# CPU_microcontroler.net
KiCad netlist of a schematic drawn in Altium Designer
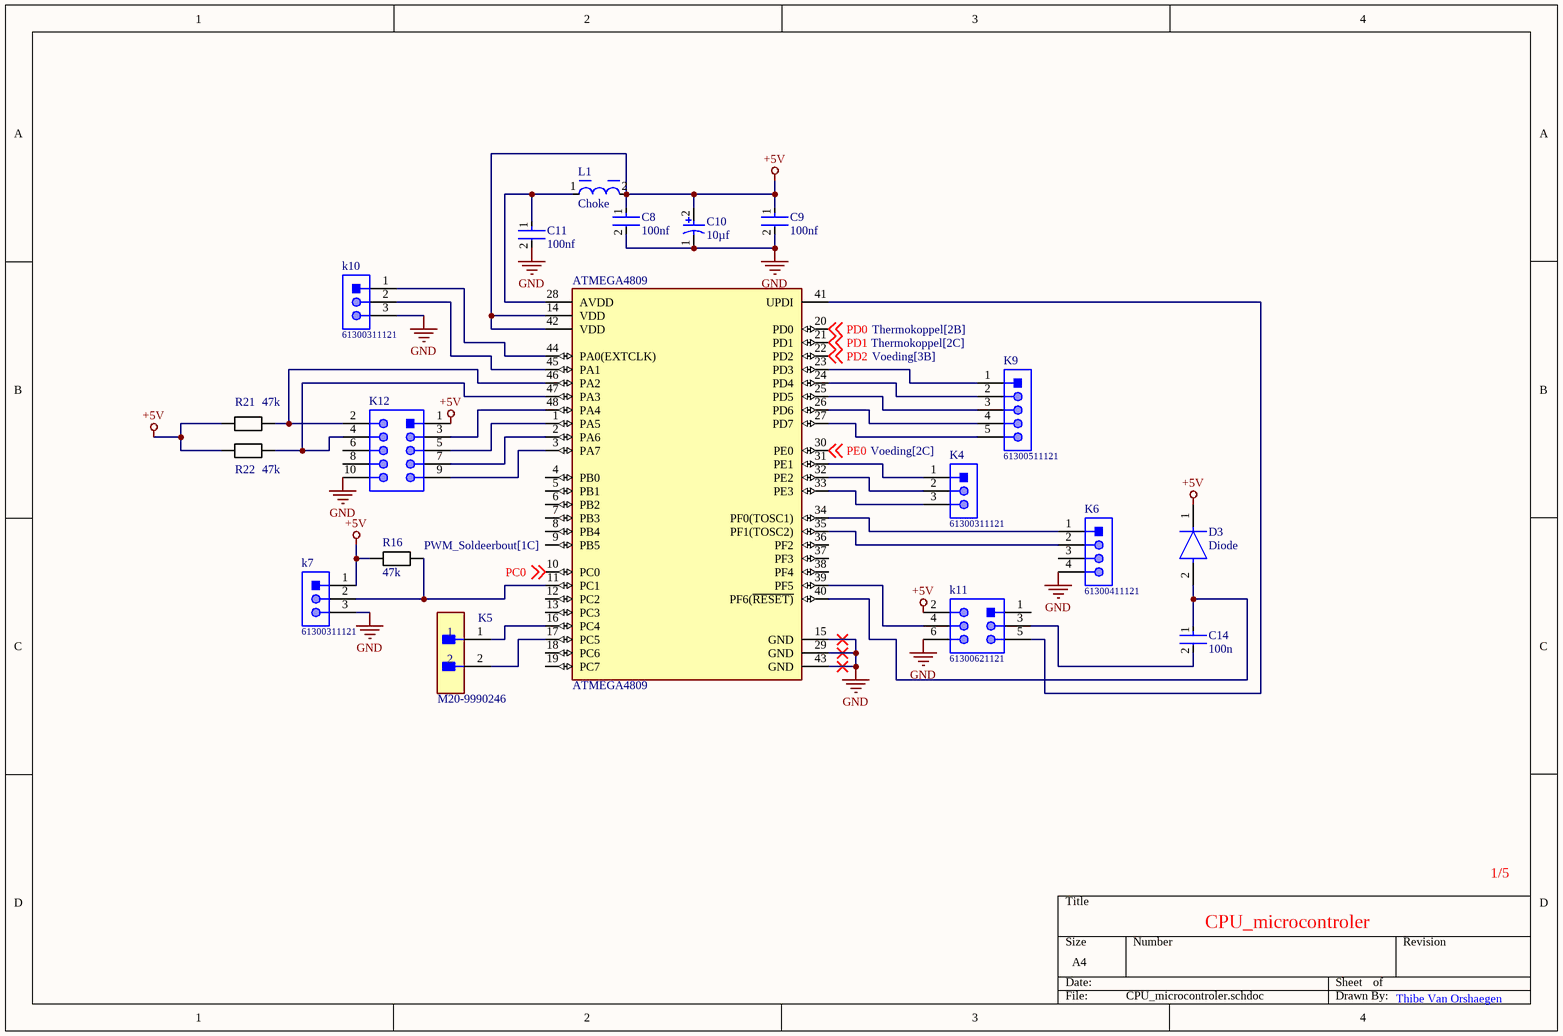
[diagram p0: CPU_microcontroler.schdoc]

(export (version "E")
  (design (tool "Eeschema 10.0.6"))
  (components
    (comp (ref "ATMEGA4809")
      (value "ATMEGA4809")
      (footprint "TQFP_48_M")
      (libsource (lib "Soldeerstation") (part "ATMEGA4809"))
    )
    (comp (ref "C8")
      (value "100nf")
      (footprint "CC_0805_m")
      (fields
        (field (name "MANUFACTURER") "KEMET")
        (field (name "OCTOPART") "https://octopart.com/c0805c224k5ractu-kemet-144670")
        (field (name "MANUFACTURER PART NUMBER") "C0805C224K5RACTU")
      )
      (libsource (lib "Soldeerstation") (part "Capacitor_Ceramic"))
    )
    (comp (ref "C9")
      (value "100nf")
      (footprint "CC_0805_m")
      (fields
        (field (name "MANUFACTURER") "KEMET")
        (field (name "OCTOPART") "https://octopart.com/c0805c224k5ractu-kemet-144670")
        (field (name "MANUFACTURER PART NUMBER") "C0805C224K5RACTU")
      )
      (libsource (lib "Soldeerstation") (part "Capacitor_Ceramic"))
    )
    (comp (ref "C10")
      (value "10µf")
      (footprint "CE_D8_L10")
      (fields (field (name "MANUFACTURER") "Panasonic"))
      (libsource (lib "Soldeerstation") (part "Capacitor_Electrolytic"))
    )
    (comp (ref "C11")
      (value "100nf")
      (footprint "CC_0805_m")
      (fields
        (field (name "MANUFACTURER") "KEMET")
        (field (name "OCTOPART") "https://octopart.com/c0805c224k5ractu-kemet-144670")
        (field (name "MANUFACTURER PART NUMBER") "C0805C224K5RACTU")
      )
      (libsource (lib "Soldeerstation") (part "Capacitor_Ceramic"))
    )
    (comp (ref "C14")
      (value "100n")
      (footprint "CC_0805_m")
      (fields
        (field (name "MANUFACTURER") "KEMET")
        (field (name "OCTOPART") "https://octopart.com/c0805c224k5ractu-kemet-144670")
        (field (name "MANUFACTURER PART NUMBER") "C0805C224K5RACTU")
      )
      (libsource (lib "Soldeerstation") (part "Capacitor_Ceramic"))
    )
    (comp (ref "D3")
      (value "Diode")
      (footprint "SOD-123FL")
      (fields
        (field (name "MANUFACTURER PART NUMBER") "1N4007")
        (field (name "MANUFACTURER") "Diotec")
        (field (name "OCTOPART") "https://octopart.com/1n4007-diotec-4040411")
      )
      (libsource (lib "Soldeerstation") (part "Diode"))
    )
    (comp (ref "K4")
      (value "61300311121")
      (footprint "pin header 1x3")
      (description "THT Vertical Pin Header WR-PHD, Pitch 2.54 mm, Single Row, 3 pins")
      (fields (field (name "MANUFACTURER") "Wurth Elektronik") (field (name "PUBLISHER") "WurthElektronik"))
      (libsource (lib "") (part "pin header 1x3pin_1"))
    )
    (comp (ref "K5")
      (value "M20-9990246")
      (footprint "pin header 1x2")
      (description "CONN HEADER VERT 2POS 2.54MM")
      (fields
        (field (name "OCTOPART") "https://octopart.com/m20-9990246-harwin-2590635")
        (field (name "MANUFACTURER") "Harwin")
      )
      (libsource (lib "Soldeerstation") (part "pin header 1x2"))
    )
    (comp (ref "K6")
      (value "61300411121")
      (footprint "pin header 1x4")
      (description "THT Vertical Pin Header WR-PHD, Pitch 2.54 mm, Single Row, 4 pins")
      (fields (field (name "MANUFACTURER") "Wurth Elektronik") (field (name "PUBLISHER") "WurthElektronik"))
      (libsource (lib "Soldeerstation") (part "pin header 1x4"))
    )
    (comp (ref "k7")
      (value "61300311121")
      (footprint "pin header 1x3")
      (description "THT Vertical Pin Header WR-PHD, Pitch 2.54 mm, Single Row, 3 pins")
      (fields (field (name "MANUFACTURER") "Wurth Elektronik") (field (name "PUBLISHER") "WurthElektronik"))
      (libsource (lib "Soldeerstation") (part "pin header 1x3pin"))
    )
    (comp (ref "K9")
      (value "61300511121")
      (footprint "pin header 1x5")
      (description "THT Vertical Pin Header WR-PHD, Pitch 2.54 mm, Single Row, 5 pins")
      (fields (field (name "MANUFACTURER") "Wurth Elektronik") (field (name "PUBLISHER") "WurthElektronik"))
      (libsource (lib "Soldeerstation") (part "pin header 1x5"))
    )
    (comp (ref "k10")
      (value "61300311121")
      (footprint "pin header 1x3")
      (description "THT Vertical Pin Header WR-PHD, Pitch 2.54 mm, Single Row, 3 pins")
      (fields (field (name "MANUFACTURER") "Wurth Elektronik") (field (name "PUBLISHER") "WurthElektronik"))
      (libsource (lib "Soldeerstation") (part "pin header 1x3pin"))
    )
    (comp (ref "k11")
      (value "61300621121")
      (footprint "pin header 2x6")
      (description "THT Vertical Pin Header WR-PHD, Pitch 2.54 mm, Dual Row, 6 pins")
      (fields (field (name "MANUFACTURER") "Wurth Elektronik") (field (name "PUBLISHER") "WurthElektronik"))
      (libsource (lib "Soldeerstation") (part "pin header 2x6"))
    )
    (comp (ref "K12")
      (value "~")
      (footprint "box header 10-pin")
      (description "Male Box Header WR-BHD, THT, Vertical, pitch 2.54 mm, 10 pins")
      (fields
        (field (name "PART NUMBER") "61201021621")
        (field (name "MANUFACTURER") "Wurth Elektronik")
        (field (name "PUBLISHER") "WurthElektronik")
      )
      (libsource (lib "Soldeerstation") (part "Box Header"))
    )
    (comp (ref "L1")
      (value "Choke")
      (footprint "CC_0805_m")
      (fields (field (name "TOLERANCE") "20%"))
      (libsource (lib "Soldeerstation") (part "Choke"))
    )
    (comp (ref "R16")
      (value "47k")
      (footprint "RESC2013X50X30ML20T20")
      (fields (field (name "MANUFACTURER") "Vishay Dale") (field (name "PART NUMBER") "CRCW08050000Z0EA"))
      (libsource (lib "Soldeerstation") (part "Weerstand"))
    )
    (comp (ref "R21")
      (value "47k")
      (footprint "RESC2013X50X30ML20T20")
      (fields (field (name "MANUFACTURER") "Vishay Dale") (field (name "PART NUMBER") "CRCW08050000Z0EA"))
      (libsource (lib "Soldeerstation") (part "Weerstand"))
    )
    (comp (ref "R22")
      (value "47k")
      (footprint "RESC2013X50X30ML20T20")
      (fields (field (name "MANUFACTURER") "Vishay Dale") (field (name "PART NUMBER") "CRCW08050000Z0EA"))
      (libsource (lib "Soldeerstation") (part "Weerstand"))
    )
  )
  (nets
    (net (code "1") (name "+5V") (class "Default")
      (node (ref "ATMEGA4809") (pin "14") (pinfunction "VDD_14") (pintype "power_in"))
      (node (ref "ATMEGA4809") (pin "42") (pinfunction "VDD_42") (pintype "power_in"))
      (node (ref "C10") (pin "2") (pinfunction "2_2") (pintype "passive"))
      (node (ref "C8") (pin "1") (pinfunction "1_1") (pintype "passive"))
      (node (ref "C9") (pin "1") (pinfunction "1_1") (pintype "passive"))
      (node (ref "D3") (pin "1") (pinfunction "C_1") (pintype "passive"))
      (node (ref "K12") (pin "1") (pinfunction "1_1") (pintype "passive"))
      (node (ref "L1") (pin "2") (pinfunction "2_2") (pintype "passive"))
      (node (ref "R16") (pin "1") (pinfunction "1_1") (pintype "passive"))
      (node (ref "R21") (pin "1") (pinfunction "1_1") (pintype "passive"))
      (node (ref "R22") (pin "1") (pinfunction "1_1") (pintype "passive"))
      (node (ref "k11") (pin "2") (pinfunction "2_2") (pintype "passive"))
      (node (ref "k7") (pin "1") (pinfunction "1_1") (pintype "passive"))
    )
    (net (code "2") (name "GND") (class "Default")
      (node (ref "ATMEGA4809") (pin "15") (pinfunction "GND_15") (pintype "open_emitter"))
      (node (ref "ATMEGA4809") (pin "29") (pinfunction "GND_29") (pintype "power_in"))
      (node (ref "ATMEGA4809") (pin "43") (pinfunction "GND_43") (pintype "power_in"))
      (node (ref "C10") (pin "1") (pinfunction "1_1") (pintype "passive"))
      (node (ref "C11") (pin "2") (pinfunction "2_2") (pintype "passive"))
      (node (ref "C8") (pin "2") (pinfunction "2_2") (pintype "passive"))
      (node (ref "C9") (pin "2") (pinfunction "2_2") (pintype "passive"))
      (node (ref "K12") (pin "10") (pinfunction "10_10") (pintype "passive"))
      (node (ref "K6") (pin "4") (pinfunction "4_4") (pintype "passive"))
      (node (ref "k10") (pin "3") (pinfunction "3_3") (pintype "passive"))
      (node (ref "k11") (pin "6") (pinfunction "6_6") (pintype "passive"))
      (node (ref "k7") (pin "3") (pinfunction "3_3") (pintype "passive"))
    )
    (net (code "3") (name "Net-(ATMEGA4809-AVDD)") (class "Default")
      (node (ref "ATMEGA4809") (pin "28") (pinfunction "AVDD_28") (pintype "power_in"))
      (node (ref "C11") (pin "1") (pinfunction "1_1") (pintype "passive"))
      (node (ref "L1") (pin "1") (pinfunction "1_1") (pintype "passive"))
    )
    (net (code "4") (name "Net-(ATMEGA4809-PA0(EXTCLK))") (class "Default")
      (node (ref "ATMEGA4809") (pin "44") (pinfunction "PA0(EXTCLK)_44") (pintype "bidirectional"))
      (node (ref "k10") (pin "1") (pinfunction "1_1") (pintype "passive"))
    )
    (net (code "5") (name "Net-(ATMEGA4809-PA1)") (class "Default")
      (node (ref "ATMEGA4809") (pin "45") (pinfunction "PA1_45") (pintype "bidirectional"))
      (node (ref "k10") (pin "2") (pinfunction "2_2") (pintype "passive"))
    )
    (net (code "6") (name "Net-(ATMEGA4809-PA2)") (class "Default")
      (node (ref "ATMEGA4809") (pin "46") (pinfunction "PA2_46") (pintype "bidirectional"))
      (node (ref "K12") (pin "2") (pinfunction "2_2") (pintype "passive"))
      (node (ref "R21") (pin "2") (pinfunction "2_2") (pintype "passive"))
    )
    (net (code "7") (name "Net-(ATMEGA4809-PA3)") (class "Default")
      (node (ref "ATMEGA4809") (pin "47") (pinfunction "PA3_47") (pintype "bidirectional"))
      (node (ref "K12") (pin "4") (pinfunction "4_4") (pintype "passive"))
      (node (ref "R22") (pin "2") (pinfunction "2_2") (pintype "passive"))
    )
    (net (code "8") (name "Net-(ATMEGA4809-PA4)") (class "Default")
      (node (ref "ATMEGA4809") (pin "48") (pinfunction "PA4_48") (pintype "bidirectional"))
      (node (ref "K12") (pin "3") (pinfunction "3_3") (pintype "passive"))
    )
    (net (code "9") (name "Net-(ATMEGA4809-PA5)") (class "Default")
      (node (ref "ATMEGA4809") (pin "1") (pinfunction "PA5_1") (pintype "bidirectional"))
      (node (ref "K12") (pin "5") (pinfunction "5_5") (pintype "passive"))
    )
    (net (code "10") (name "Net-(ATMEGA4809-PA6)") (class "Default")
      (node (ref "ATMEGA4809") (pin "2") (pinfunction "PA6_2") (pintype "bidirectional"))
      (node (ref "K12") (pin "7") (pinfunction "7_7") (pintype "passive"))
    )
    (net (code "11") (name "Net-(ATMEGA4809-PA7)") (class "Default")
      (node (ref "ATMEGA4809") (pin "3") (pinfunction "PA7_3") (pintype "bidirectional"))
      (node (ref "K12") (pin "9") (pinfunction "9_9") (pintype "passive"))
    )
    (net (code "12") (name "Net-(ATMEGA4809-PC1)") (class "Default")
      (node (ref "ATMEGA4809") (pin "11") (pinfunction "PC1_11") (pintype "bidirectional"))
      (node (ref "R16") (pin "2") (pinfunction "2_2") (pintype "passive"))
      (node (ref "k7") (pin "2") (pinfunction "2_2") (pintype "passive"))
    )
    (net (code "13") (name "Net-(ATMEGA4809-PC4)") (class "Default")
      (node (ref "ATMEGA4809") (pin "16") (pinfunction "PC4_16") (pintype "bidirectional"))
      (node (ref "K5") (pin "1") (pinfunction "1_1") (pintype "passive"))
    )
    (net (code "14") (name "Net-(ATMEGA4809-PC5)") (class "Default")
      (node (ref "ATMEGA4809") (pin "17") (pinfunction "PC5_17") (pintype "bidirectional"))
      (node (ref "K5") (pin "2") (pinfunction "2_2") (pintype "passive"))
    )
    (net (code "15") (name "Net-(ATMEGA4809-PD3)") (class "Default")
      (node (ref "ATMEGA4809") (pin "23") (pinfunction "PD3_23") (pintype "bidirectional"))
      (node (ref "K9") (pin "1") (pinfunction "1_1") (pintype "passive"))
    )
    (net (code "16") (name "Net-(ATMEGA4809-PD4)") (class "Default")
      (node (ref "ATMEGA4809") (pin "24") (pinfunction "PD4_24") (pintype "bidirectional"))
      (node (ref "K9") (pin "2") (pinfunction "2_2") (pintype "passive"))
    )
    (net (code "17") (name "Net-(ATMEGA4809-PD5)") (class "Default")
      (node (ref "ATMEGA4809") (pin "25") (pinfunction "PD5_25") (pintype "bidirectional"))
      (node (ref "K9") (pin "3") (pinfunction "3_3") (pintype "passive"))
    )
    (net (code "18") (name "Net-(ATMEGA4809-PD6)") (class "Default")
      (node (ref "ATMEGA4809") (pin "26") (pinfunction "PD6_26") (pintype "bidirectional"))
      (node (ref "K9") (pin "4") (pinfunction "4_4") (pintype "passive"))
    )
    (net (code "19") (name "Net-(ATMEGA4809-PD7)") (class "Default")
      (node (ref "ATMEGA4809") (pin "27") (pinfunction "PD7_27") (pintype "bidirectional"))
      (node (ref "K9") (pin "5") (pinfunction "5_5") (pintype "passive"))
    )
    (net (code "20") (name "Net-(ATMEGA4809-PE1)") (class "Default")
      (node (ref "ATMEGA4809") (pin "31") (pinfunction "PE1_31") (pintype "bidirectional"))
      (node (ref "K4") (pin "1") (pinfunction "1_1") (pintype "passive"))
    )
    (net (code "21") (name "Net-(ATMEGA4809-PE2)") (class "Default")
      (node (ref "ATMEGA4809") (pin "32") (pinfunction "PE2_32") (pintype "bidirectional"))
      (node (ref "K4") (pin "2") (pinfunction "2_2") (pintype "passive"))
    )
    (net (code "22") (name "Net-(ATMEGA4809-PE3)") (class "Default")
      (node (ref "ATMEGA4809") (pin "33") (pinfunction "PE3_33") (pintype "bidirectional"))
      (node (ref "K4") (pin "3") (pinfunction "3_3") (pintype "passive"))
    )
    (net (code "23") (name "Net-(ATMEGA4809-PF0(TOSC1))") (class "Default")
      (node (ref "ATMEGA4809") (pin "34") (pinfunction "PF0(TOSC1)_34") (pintype "bidirectional"))
      (node (ref "K6") (pin "1") (pinfunction "1_1") (pintype "passive"))
    )
    (net (code "24") (name "Net-(ATMEGA4809-PF1(TOSC2))") (class "Default")
      (node (ref "ATMEGA4809") (pin "35") (pinfunction "PF1(TOSC2)_35") (pintype "bidirectional"))
      (node (ref "K6") (pin "2") (pinfunction "2_2") (pintype "passive"))
    )
    (net (code "25") (name "Net-(ATMEGA4809-PF5)") (class "Default")
      (node (ref "ATMEGA4809") (pin "39") (pinfunction "PF5_39") (pintype "bidirectional"))
      (node (ref "k11") (pin "4") (pinfunction "4_4") (pintype "passive"))
    )
    (net (code "26") (name "Net-(ATMEGA4809-PF6(~{RESET)})") (class "Default")
      (node (ref "ATMEGA4809") (pin "40") (pinfunction "PF6(~{RESET)}_40") (pintype "bidirectional"))
      (node (ref "C14") (pin "1") (pinfunction "1_1") (pintype "passive"))
      (node (ref "D3") (pin "2") (pinfunction "A_2") (pintype "passive"))
    )
    (net (code "27") (name "Net-(ATMEGA4809-UPDI)") (class "Default")
      (node (ref "ATMEGA4809") (pin "41") (pinfunction "UPDI_41") (pintype "passive"))
      (node (ref "k11") (pin "5") (pinfunction "5_5") (pintype "passive"))
    )
    (net (code "28") (name "Net-(C14-Pad2)") (class "Default")
      (node (ref "C14") (pin "2") (pinfunction "2_2") (pintype "passive"))
      (node (ref "k11") (pin "3") (pinfunction "3_3") (pintype "passive"))
    )
    (net (code "29") (name "PC0") (class "Default")
      (node (ref "ATMEGA4809") (pin "10") (pinfunction "PC0_10") (pintype "bidirectional"))
    )
    (net (code "30") (name "PD0") (class "Default")
      (node (ref "ATMEGA4809") (pin "20") (pinfunction "PD0_20") (pintype "bidirectional"))
    )
    (net (code "31") (name "PD1") (class "Default")
      (node (ref "ATMEGA4809") (pin "21") (pinfunction "PD1_21") (pintype "bidirectional"))
    )
    (net (code "32") (name "PD2") (class "Default")
      (node (ref "ATMEGA4809") (pin "22") (pinfunction "PD2_22") (pintype "bidirectional"))
    )
    (net (code "33") (name "PE0") (class "Default")
      (node (ref "ATMEGA4809") (pin "30") (pinfunction "PE0_30") (pintype "bidirectional"))
    )
    (net (code "34") (name "unconnected-(ATMEGA4809-PB0-Pad4)") (class "Default")
      (node (ref "ATMEGA4809") (pin "4") (pinfunction "PB0_4") (pintype "bidirectional"))
    )
    (net (code "35") (name "unconnected-(ATMEGA4809-PB1-Pad5)") (class "Default")
      (node (ref "ATMEGA4809") (pin "5") (pinfunction "PB1_5") (pintype "bidirectional"))
    )
    (net (code "36") (name "unconnected-(ATMEGA4809-PB2-Pad6)") (class "Default")
      (node (ref "ATMEGA4809") (pin "6") (pinfunction "PB2_6") (pintype "bidirectional"))
    )
    (net (code "37") (name "unconnected-(ATMEGA4809-PB3-Pad7)") (class "Default")
      (node (ref "ATMEGA4809") (pin "7") (pinfunction "PB3_7") (pintype "bidirectional"))
    )
    (net (code "38") (name "unconnected-(ATMEGA4809-PB4-Pad8)") (class "Default")
      (node (ref "ATMEGA4809") (pin "8") (pinfunction "PB4_8") (pintype "bidirectional"))
    )
    (net (code "39") (name "unconnected-(ATMEGA4809-PB5-Pad9)") (class "Default")
      (node (ref "ATMEGA4809") (pin "9") (pinfunction "PB5_9") (pintype "bidirectional"))
    )
    (net (code "40") (name "unconnected-(ATMEGA4809-PC2-Pad12)") (class "Default")
      (node (ref "ATMEGA4809") (pin "12") (pinfunction "PC2_12") (pintype "bidirectional"))
    )
    (net (code "41") (name "unconnected-(ATMEGA4809-PC3-Pad13)") (class "Default")
      (node (ref "ATMEGA4809") (pin "13") (pinfunction "PC3_13") (pintype "bidirectional"))
    )
    (net (code "42") (name "unconnected-(ATMEGA4809-PC6-Pad18)") (class "Default")
      (node (ref "ATMEGA4809") (pin "18") (pinfunction "PC6_18") (pintype "bidirectional"))
    )
    (net (code "43") (name "unconnected-(ATMEGA4809-PC7-Pad19)") (class "Default")
      (node (ref "ATMEGA4809") (pin "19") (pinfunction "PC7_19") (pintype "bidirectional"))
    )
    (net (code "44") (name "unconnected-(ATMEGA4809-PF2-Pad36)") (class "Default")
      (node (ref "ATMEGA4809") (pin "36") (pinfunction "PF2_36") (pintype "bidirectional"))
    )
    (net (code "45") (name "unconnected-(ATMEGA4809-PF3-Pad37)") (class "Default")
      (node (ref "ATMEGA4809") (pin "37") (pinfunction "PF3_37") (pintype "bidirectional"))
    )
    (net (code "46") (name "unconnected-(ATMEGA4809-PF4-Pad38)") (class "Default")
      (node (ref "ATMEGA4809") (pin "38") (pinfunction "PF4_38") (pintype "bidirectional"))
    )
    (net (code "47") (name "unconnected-(K6-Pad3)") (class "Default")
      (node (ref "K6") (pin "3") (pinfunction "3_3") (pintype "passive"))
    )
    (net (code "48") (name "unconnected-(K12-Pad6)") (class "Default")
      (node (ref "K12") (pin "6") (pinfunction "6_6") (pintype "passive"))
    )
    (net (code "49") (name "unconnected-(K12-Pad8)") (class "Default")
      (node (ref "K12") (pin "8") (pinfunction "8_8") (pintype "passive"))
    )
    (net (code "50") (name "unconnected-(k11-Pad1)") (class "Default")
      (node (ref "k11") (pin "1") (pinfunction "1_1") (pintype "passive"))
    )
  )
)
